# GPIO.net
KiCad netlist of a schematic drawn in Altium Designer
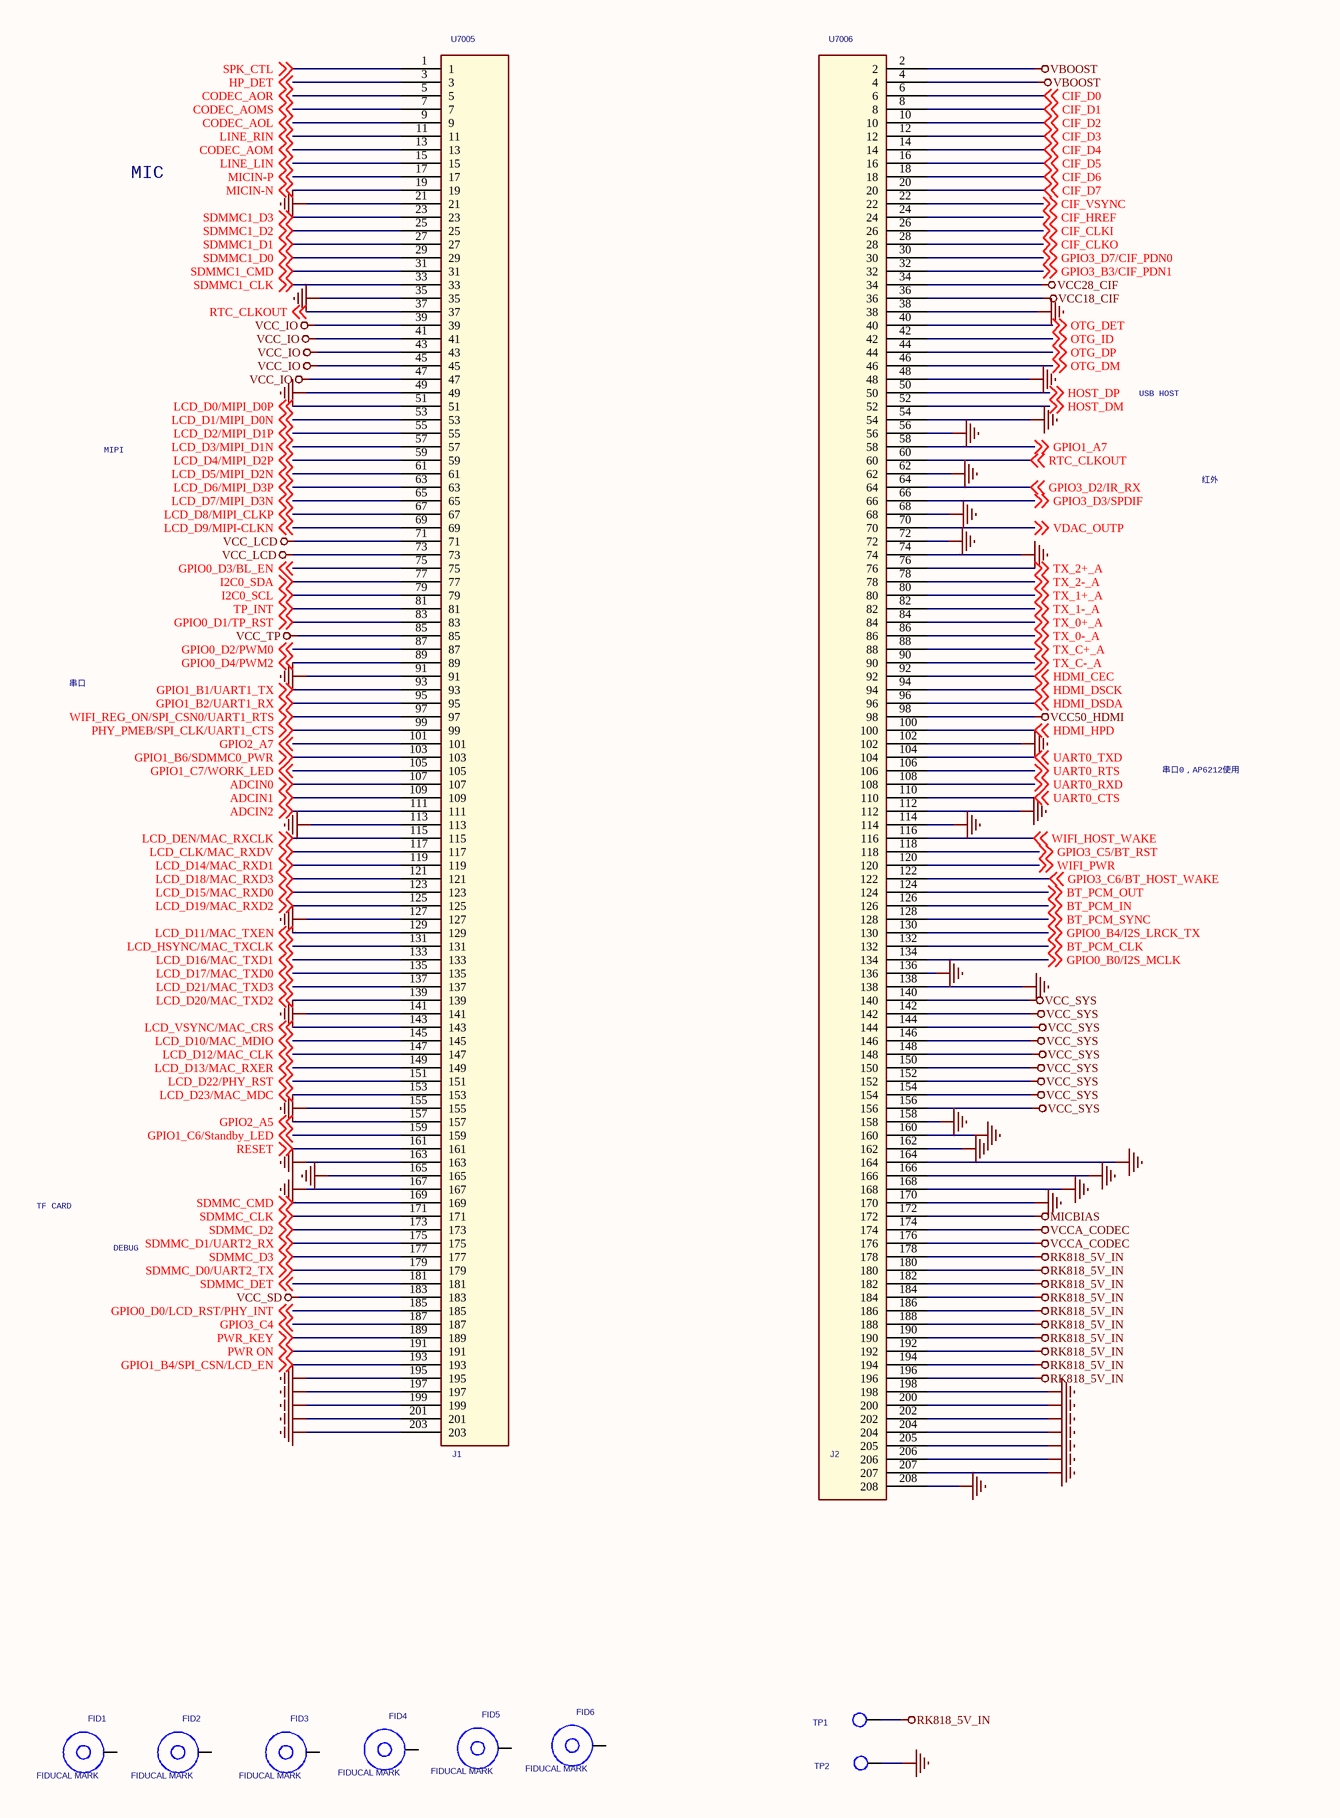
[diagram p0: GPIO.SchDoc, left]
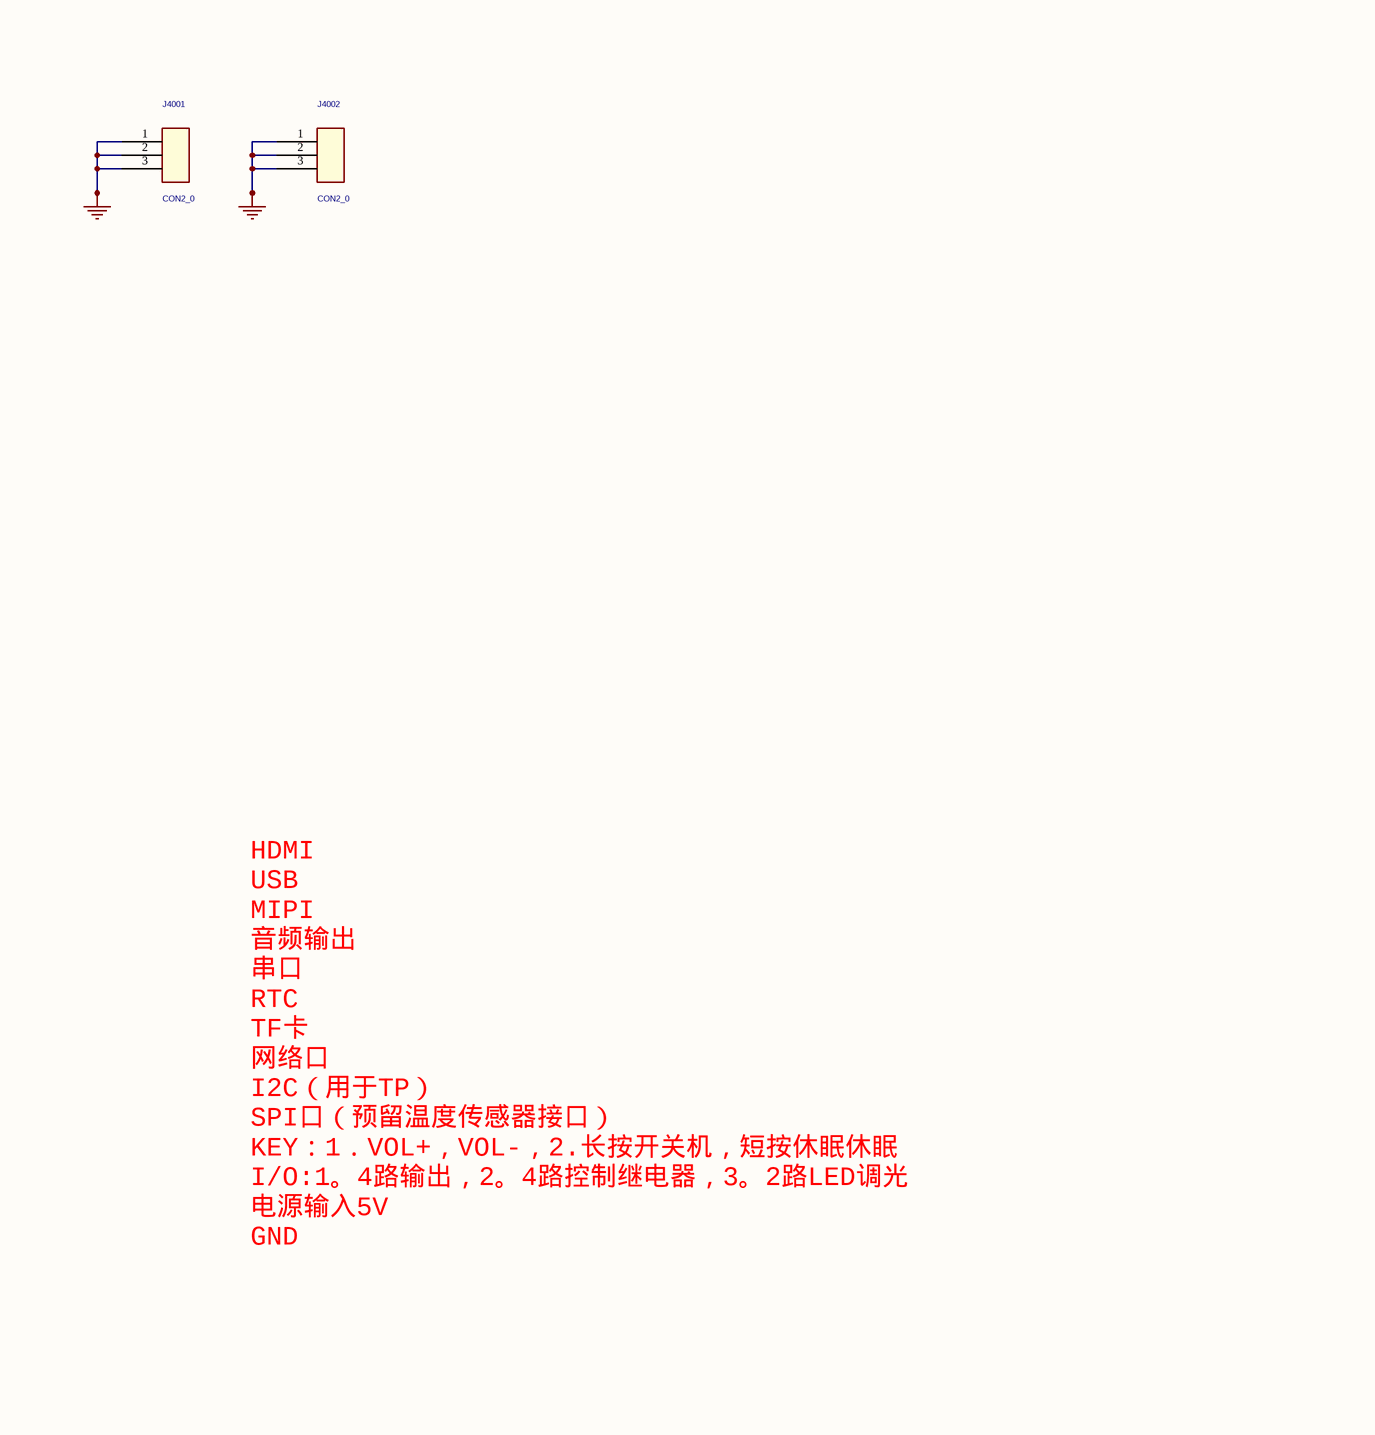
[diagram p1: GPIO.SchDoc, right]

(export (version "E")
  (design (tool "Eeschema 10.0.6"))
  (components
    (comp (ref "FID1")
      (value "FIDUCAL MARK")
      (footprint "FIDICALMARK")
      (libsource (lib "*") (part "T POINT R_2"))
    )
    (comp (ref "FID2")
      (value "FIDUCAL MARK")
      (footprint "FIDICALMARK")
      (libsource (lib "*") (part "T POINT R_2"))
    )
    (comp (ref "FID3")
      (value "FIDUCAL MARK")
      (footprint "FIDICALMARK")
      (libsource (lib "*") (part "T POINT R_2"))
    )
    (comp (ref "FID4")
      (value "FIDUCAL MARK")
      (footprint "FIDICALMARK")
      (libsource (lib "*") (part "T POINT R_2"))
    )
    (comp (ref "FID5")
      (value "FIDUCAL MARK")
      (footprint "FIDICALMARK")
      (libsource (lib "*") (part "T POINT R_2"))
    )
    (comp (ref "FID6")
      (value "FIDUCAL MARK")
      (footprint "FIDICALMARK")
      (libsource (lib "*") (part "T POINT R_2"))
    )
    (comp (ref "J4001") (value "CON2_0") (footprint "PAD_0D8X6D5_1") (libsource (lib "*") (part "CON2_1")))
    (comp (ref "J4002") (value "CON2_0") (footprint "PAD_0D8X6D5_1") (libsource (lib "*") (part "CON2_1")))
    (comp (ref "TP1") (value "T_POINT_R") (footprint "TP_PAD") (libsource (lib "*") (part "T_POINT_R")))
    (comp (ref "TP2") (value "T_POINT_R") (footprint "TP_PAD") (libsource (lib "*") (part "T_POINT_R")))
    (comp (ref "U7005") (value "J1") (footprint "2013311-1") (libsource (lib "*") (part "J1_0")))
    (comp (ref "U7006") (value "J2") (footprint "2013311-2") (libsource (lib "*") (part "J2_1")))
  )
  (nets
    (net (code "1") (name "ADCIN0") (class "Default")
      (node (ref "U7005") (pin "107") (pinfunction "107_107") (pintype "passive"))
    )
    (net (code "2") (name "ADCIN1") (class "Default")
      (node (ref "U7005") (pin "109") (pinfunction "109_109") (pintype "passive"))
    )
    (net (code "3") (name "ADCIN2") (class "Default")
      (node (ref "U7005") (pin "111") (pinfunction "111_111") (pintype "passive"))
    )
    (net (code "4") (name "BT_PCM_CLK") (class "Default")
      (node (ref "U7006") (pin "132") (pinfunction "132_132") (pintype "passive"))
    )
    (net (code "5") (name "BT_PCM_IN") (class "Default")
      (node (ref "U7006") (pin "126") (pinfunction "126_126") (pintype "passive"))
    )
    (net (code "6") (name "BT_PCM_OUT") (class "Default")
      (node (ref "U7006") (pin "124") (pinfunction "124_124") (pintype "passive"))
    )
    (net (code "7") (name "BT_PCM_SYNC") (class "Default")
      (node (ref "U7006") (pin "128") (pinfunction "128_128") (pintype "passive"))
    )
    (net (code "8") (name "CIF_CLKI") (class "Default")
      (node (ref "U7006") (pin "26") (pinfunction "26_26") (pintype "passive"))
    )
    (net (code "9") (name "CIF_CLKO") (class "Default")
      (node (ref "U7006") (pin "28") (pinfunction "28_28") (pintype "passive"))
    )
    (net (code "10") (name "CIF_D0") (class "Default")
      (node (ref "U7006") (pin "6") (pinfunction "6_6") (pintype "passive"))
    )
    (net (code "11") (name "CIF_D1") (class "Default")
      (node (ref "U7006") (pin "8") (pinfunction "8_8") (pintype "passive"))
    )
    (net (code "12") (name "CIF_D2") (class "Default")
      (node (ref "U7006") (pin "10") (pinfunction "10_10") (pintype "passive"))
    )
    (net (code "13") (name "CIF_D3") (class "Default")
      (node (ref "U7006") (pin "12") (pinfunction "12_12") (pintype "passive"))
    )
    (net (code "14") (name "CIF_D4") (class "Default")
      (node (ref "U7006") (pin "14") (pinfunction "14_14") (pintype "passive"))
    )
    (net (code "15") (name "CIF_D5") (class "Default")
      (node (ref "U7006") (pin "16") (pinfunction "16_16") (pintype "passive"))
    )
    (net (code "16") (name "CIF_D6") (class "Default")
      (node (ref "U7006") (pin "18") (pinfunction "18_18") (pintype "passive"))
    )
    (net (code "17") (name "CIF_D7") (class "Default")
      (node (ref "U7006") (pin "20") (pinfunction "20_20") (pintype "passive"))
    )
    (net (code "18") (name "CIF_HREF") (class "Default")
      (node (ref "U7006") (pin "24") (pinfunction "24_24") (pintype "passive"))
    )
    (net (code "19") (name "CIF_VSYNC") (class "Default")
      (node (ref "U7006") (pin "22") (pinfunction "22_22") (pintype "passive"))
    )
    (net (code "20") (name "CODEC_AOL") (class "Default")
      (node (ref "U7005") (pin "9") (pinfunction "9_9") (pintype "passive"))
    )
    (net (code "21") (name "CODEC_AOM") (class "Default")
      (node (ref "U7005") (pin "13") (pinfunction "13_13") (pintype "passive"))
    )
    (net (code "22") (name "CODEC_AOMS") (class "Default")
      (node (ref "U7005") (pin "7") (pinfunction "7_7") (pintype "passive"))
    )
    (net (code "23") (name "CODEC_AOR") (class "Default")
      (node (ref "U7005") (pin "5") (pinfunction "5_5") (pintype "passive"))
    )
    (net (code "24") (name "GND") (class "Default")
      (node (ref "J4001") (pin "1") (pinfunction "1_1") (pintype "passive"))
      (node (ref "J4001") (pin "2") (pinfunction "2_2") (pintype "passive"))
      (node (ref "J4001") (pin "3") (pinfunction "3_3") (pintype "passive"))
      (node (ref "J4002") (pin "1") (pinfunction "1_1") (pintype "passive"))
      (node (ref "J4002") (pin "2") (pinfunction "2_2") (pintype "passive"))
      (node (ref "J4002") (pin "3") (pinfunction "3_3") (pintype "passive"))
      (node (ref "TP2") (pin "1") (pinfunction "TP_1") (pintype "passive"))
      (node (ref "U7005") (pin "113") (pinfunction "113_113") (pintype "passive"))
      (node (ref "U7005") (pin "127") (pinfunction "127_127") (pintype "passive"))
      (node (ref "U7005") (pin "141") (pinfunction "141_141") (pintype "passive"))
      (node (ref "U7005") (pin "155") (pinfunction "155_155") (pintype "passive"))
      (node (ref "U7005") (pin "163") (pinfunction "163_163") (pintype "passive"))
      (node (ref "U7005") (pin "165") (pinfunction "165_165") (pintype "passive"))
      (node (ref "U7005") (pin "167") (pinfunction "167_167") (pintype "passive"))
      (node (ref "U7005") (pin "195") (pinfunction "195_195") (pintype "passive"))
      (node (ref "U7005") (pin "197") (pinfunction "197_197") (pintype "passive"))
      (node (ref "U7005") (pin "199") (pinfunction "199_199") (pintype "passive"))
      (node (ref "U7005") (pin "201") (pinfunction "201_201") (pintype "passive"))
      (node (ref "U7005") (pin "203") (pinfunction "203_203") (pintype "passive"))
      (node (ref "U7005") (pin "21") (pinfunction "21_21") (pintype "passive"))
      (node (ref "U7005") (pin "35") (pinfunction "35_35") (pintype "passive"))
      (node (ref "U7005") (pin "49") (pinfunction "49_49") (pintype "passive"))
      (node (ref "U7005") (pin "91") (pinfunction "91_91") (pintype "passive"))
      (node (ref "U7006") (pin "102") (pinfunction "102_102") (pintype "passive"))
      (node (ref "U7006") (pin "112") (pinfunction "112_112") (pintype "passive"))
      (node (ref "U7006") (pin "114") (pinfunction "114_114") (pintype "passive"))
      (node (ref "U7006") (pin "136") (pinfunction "136_136") (pintype "passive"))
      (node (ref "U7006") (pin "138") (pinfunction "138_138") (pintype "passive"))
      (node (ref "U7006") (pin "158") (pinfunction "158_158") (pintype "passive"))
      (node (ref "U7006") (pin "160") (pinfunction "160_160") (pintype "passive"))
      (node (ref "U7006") (pin "162") (pinfunction "162_162") (pintype "passive"))
      (node (ref "U7006") (pin "164") (pinfunction "164_164") (pintype "passive"))
      (node (ref "U7006") (pin "166") (pinfunction "166_166") (pintype "passive"))
      (node (ref "U7006") (pin "168") (pinfunction "168_168") (pintype "passive"))
      (node (ref "U7006") (pin "170") (pinfunction "170_170") (pintype "passive"))
      (node (ref "U7006") (pin "198") (pinfunction "198_198") (pintype "passive"))
      (node (ref "U7006") (pin "200") (pinfunction "200_200") (pintype "passive"))
      (node (ref "U7006") (pin "202") (pinfunction "202_202") (pintype "passive"))
      (node (ref "U7006") (pin "204") (pinfunction "204_204") (pintype "passive"))
      (node (ref "U7006") (pin "205") (pinfunction "205_205") (pintype "passive"))
      (node (ref "U7006") (pin "206") (pinfunction "206_206") (pintype "passive"))
      (node (ref "U7006") (pin "207") (pinfunction "207_207") (pintype "passive"))
      (node (ref "U7006") (pin "208") (pinfunction "208_208") (pintype "passive"))
      (node (ref "U7006") (pin "38") (pinfunction "38_38") (pintype "passive"))
      (node (ref "U7006") (pin "48") (pinfunction "48_48") (pintype "passive"))
      (node (ref "U7006") (pin "54") (pinfunction "54_54") (pintype "passive"))
      (node (ref "U7006") (pin "56") (pinfunction "56_56") (pintype "passive"))
      (node (ref "U7006") (pin "62") (pinfunction "62_62") (pintype "passive"))
      (node (ref "U7006") (pin "68") (pinfunction "68_68") (pintype "passive"))
      (node (ref "U7006") (pin "72") (pinfunction "72_72") (pintype "passive"))
      (node (ref "U7006") (pin "74") (pinfunction "74_74") (pintype "passive"))
    )
    (net (code "25") (name "GPIO0_B0{slash}I2S_MCLK") (class "Default")
      (node (ref "U7006") (pin "134") (pinfunction "134_134") (pintype "passive"))
    )
    (net (code "26") (name "GPIO0_B4{slash}I2S_LRCK_TX") (class "Default")
      (node (ref "U7006") (pin "130") (pinfunction "130_130") (pintype "passive"))
    )
    (net (code "27") (name "GPIO0_D0{slash}LCD_RST{slash}PHY_INT") (class "Default")
      (node (ref "U7005") (pin "185") (pinfunction "185_185") (pintype "passive"))
    )
    (net (code "28") (name "GPIO0_D1{slash}TP_RST") (class "Default")
      (node (ref "U7005") (pin "83") (pinfunction "83_83") (pintype "passive"))
    )
    (net (code "29") (name "GPIO0_D2{slash}PWM0") (class "Default")
      (node (ref "U7005") (pin "87") (pinfunction "87_87") (pintype "passive"))
    )
    (net (code "30") (name "GPIO0_D3{slash}BL_EN") (class "Default")
      (node (ref "U7005") (pin "75") (pinfunction "75_75") (pintype "passive"))
    )
    (net (code "31") (name "GPIO0_D4{slash}PWM2") (class "Default")
      (node (ref "U7005") (pin "89") (pinfunction "89_89") (pintype "passive"))
    )
    (net (code "32") (name "GPIO1_A7") (class "Default")
      (node (ref "U7006") (pin "58") (pinfunction "58_58") (pintype "passive"))
    )
    (net (code "33") (name "GPIO1_B1{slash}UART1_TX") (class "Default")
      (node (ref "U7005") (pin "93") (pinfunction "93_93") (pintype "passive"))
    )
    (net (code "34") (name "GPIO1_B2{slash}UART1_RX") (class "Default")
      (node (ref "U7005") (pin "95") (pinfunction "95_95") (pintype "passive"))
    )
    (net (code "35") (name "GPIO1_B4{slash}SPI_CSN{slash}LCD_EN") (class "Default")
      (node (ref "U7005") (pin "193") (pinfunction "193_193") (pintype "passive"))
    )
    (net (code "36") (name "GPIO1_B6{slash}SDMMC0_PWR") (class "Default")
      (node (ref "U7005") (pin "103") (pinfunction "103_103") (pintype "passive"))
    )
    (net (code "37") (name "GPIO1_C6{slash}Standby_LED") (class "Default")
      (node (ref "U7005") (pin "159") (pinfunction "159_159") (pintype "passive"))
    )
    (net (code "38") (name "GPIO1_C7{slash}WORK_LED") (class "Default")
      (node (ref "U7005") (pin "105") (pinfunction "105_105") (pintype "passive"))
    )
    (net (code "39") (name "GPIO2_A5") (class "Default")
      (node (ref "U7005") (pin "157") (pinfunction "157_157") (pintype "passive"))
    )
    (net (code "40") (name "GPIO2_A7") (class "Default")
      (node (ref "U7005") (pin "101") (pinfunction "101_101") (pintype "passive"))
    )
    (net (code "41") (name "GPIO3_B3{slash}CIF_PDN1") (class "Default")
      (node (ref "U7006") (pin "32") (pinfunction "32_32") (pintype "passive"))
    )
    (net (code "42") (name "GPIO3_C4") (class "Default")
      (node (ref "U7005") (pin "187") (pinfunction "187_187") (pintype "passive"))
    )
    (net (code "43") (name "GPIO3_C5{slash}BT_RST") (class "Default")
      (node (ref "U7006") (pin "118") (pinfunction "118_118") (pintype "passive"))
    )
    (net (code "44") (name "GPIO3_C6{slash}BT_HOST_WAKE") (class "Default")
      (node (ref "U7006") (pin "122") (pinfunction "122_122") (pintype "passive"))
    )
    (net (code "45") (name "GPIO3_D2{slash}IR_RX") (class "Default")
      (node (ref "U7006") (pin "64") (pinfunction "64_64") (pintype "passive"))
    )
    (net (code "46") (name "GPIO3_D3{slash}SPDIF") (class "Default")
      (node (ref "U7006") (pin "66") (pinfunction "66_66") (pintype "passive"))
    )
    (net (code "47") (name "GPIO3_D7{slash}CIF_PDN0") (class "Default")
      (node (ref "U7006") (pin "30") (pinfunction "30_30") (pintype "passive"))
    )
    (net (code "48") (name "HDMI_CEC") (class "Default")
      (node (ref "U7006") (pin "92") (pinfunction "92_92") (pintype "passive"))
    )
    (net (code "49") (name "HDMI_DSCK") (class "Default")
      (node (ref "U7006") (pin "94") (pinfunction "94_94") (pintype "passive"))
    )
    (net (code "50") (name "HDMI_DSDA") (class "Default")
      (node (ref "U7006") (pin "96") (pinfunction "96_96") (pintype "passive"))
    )
    (net (code "51") (name "HDMI_HPD") (class "Default")
      (node (ref "U7006") (pin "100") (pinfunction "100_100") (pintype "passive"))
    )
    (net (code "52") (name "HOST_DM") (class "Default")
      (node (ref "U7006") (pin "52") (pinfunction "52_52") (pintype "passive"))
    )
    (net (code "53") (name "HOST_DP") (class "Default")
      (node (ref "U7006") (pin "50") (pinfunction "50_50") (pintype "passive"))
    )
    (net (code "54") (name "HP_DET") (class "Default")
      (node (ref "U7005") (pin "3") (pinfunction "3_3") (pintype "passive"))
    )
    (net (code "55") (name "I2C0_SCL") (class "Default")
      (node (ref "U7005") (pin "79") (pinfunction "79_79") (pintype "passive"))
    )
    (net (code "56") (name "I2C0_SDA") (class "Default")
      (node (ref "U7005") (pin "77") (pinfunction "77_77") (pintype "passive"))
    )
    (net (code "57") (name "LCD_CLK{slash}MAC_RXDV") (class "Default")
      (node (ref "U7005") (pin "117") (pinfunction "117_117") (pintype "passive"))
    )
    (net (code "58") (name "LCD_D0{slash}MIPI_D0P") (class "Default")
      (node (ref "U7005") (pin "51") (pinfunction "51_51") (pintype "passive"))
    )
    (net (code "59") (name "LCD_D1{slash}MIPI_D0N") (class "Default")
      (node (ref "U7005") (pin "53") (pinfunction "53_53") (pintype "passive"))
    )
    (net (code "60") (name "LCD_D2{slash}MIPI_D1P") (class "Default")
      (node (ref "U7005") (pin "55") (pinfunction "55_55") (pintype "passive"))
    )
    (net (code "61") (name "LCD_D3{slash}MIPI_D1N") (class "Default")
      (node (ref "U7005") (pin "57") (pinfunction "57_57") (pintype "passive"))
    )
    (net (code "62") (name "LCD_D4{slash}MIPI_D2P") (class "Default")
      (node (ref "U7005") (pin "59") (pinfunction "59_59") (pintype "passive"))
    )
    (net (code "63") (name "LCD_D5{slash}MIPI_D2N") (class "Default")
      (node (ref "U7005") (pin "61") (pinfunction "61_61") (pintype "passive"))
    )
    (net (code "64") (name "LCD_D6{slash}MIPI_D3P") (class "Default")
      (node (ref "U7005") (pin "63") (pinfunction "63_63") (pintype "passive"))
    )
    (net (code "65") (name "LCD_D7{slash}MIPI_D3N") (class "Default")
      (node (ref "U7005") (pin "65") (pinfunction "65_65") (pintype "passive"))
    )
    (net (code "66") (name "LCD_D8{slash}MIPI_CLKP") (class "Default")
      (node (ref "U7005") (pin "67") (pinfunction "67_67") (pintype "passive"))
    )
    (net (code "67") (name "LCD_D9{slash}MIPI-CLKN") (class "Default")
      (node (ref "U7005") (pin "69") (pinfunction "69_69") (pintype "passive"))
    )
    (net (code "68") (name "LCD_D10{slash}MAC_MDIO") (class "Default")
      (node (ref "U7005") (pin "145") (pinfunction "145_145") (pintype "passive"))
    )
    (net (code "69") (name "LCD_D11{slash}MAC_TXEN") (class "Default")
      (node (ref "U7005") (pin "129") (pinfunction "129_129") (pintype "passive"))
    )
    (net (code "70") (name "LCD_D12{slash}MAC_CLK") (class "Default")
      (node (ref "U7005") (pin "147") (pinfunction "147_147") (pintype "passive"))
    )
    (net (code "71") (name "LCD_D13{slash}MAC_RXER") (class "Default")
      (node (ref "U7005") (pin "149") (pinfunction "149_149") (pintype "passive"))
    )
    (net (code "72") (name "LCD_D14{slash}MAC_RXD1") (class "Default")
      (node (ref "U7005") (pin "119") (pinfunction "119_119") (pintype "passive"))
    )
    (net (code "73") (name "LCD_D15{slash}MAC_RXD0") (class "Default")
      (node (ref "U7005") (pin "123") (pinfunction "123_123") (pintype "passive"))
    )
    (net (code "74") (name "LCD_D16{slash}MAC_TXD1") (class "Default")
      (node (ref "U7005") (pin "133") (pinfunction "133_133") (pintype "passive"))
    )
    (net (code "75") (name "LCD_D17{slash}MAC_TXD0") (class "Default")
      (node (ref "U7005") (pin "135") (pinfunction "135_135") (pintype "passive"))
    )
    (net (code "76") (name "LCD_D18{slash}MAC_RXD3") (class "Default")
      (node (ref "U7005") (pin "121") (pinfunction "121_121") (pintype "passive"))
    )
    (net (code "77") (name "LCD_D19{slash}MAC_RXD2") (class "Default")
      (node (ref "U7005") (pin "125") (pinfunction "125_125") (pintype "passive"))
    )
    (net (code "78") (name "LCD_D20{slash}MAC_TXD2") (class "Default")
      (node (ref "U7005") (pin "139") (pinfunction "139_139") (pintype "passive"))
    )
    (net (code "79") (name "LCD_D21{slash}MAC_TXD3") (class "Default")
      (node (ref "U7005") (pin "137") (pinfunction "137_137") (pintype "passive"))
    )
    (net (code "80") (name "LCD_D22{slash}PHY_RST") (class "Default")
      (node (ref "U7005") (pin "151") (pinfunction "151_151") (pintype "passive"))
    )
    (net (code "81") (name "LCD_D23{slash}MAC_MDC") (class "Default")
      (node (ref "U7005") (pin "153") (pinfunction "153_153") (pintype "passive"))
    )
    (net (code "82") (name "LCD_DEN{slash}MAC_RXCLK") (class "Default")
      (node (ref "U7005") (pin "115") (pinfunction "115_115") (pintype "passive"))
    )
    (net (code "83") (name "LCD_HSYNC{slash}MAC_TXCLK") (class "Default")
      (node (ref "U7005") (pin "131") (pinfunction "131_131") (pintype "passive"))
    )
    (net (code "84") (name "LCD_VSYNC{slash}MAC_CRS") (class "Default")
      (node (ref "U7005") (pin "143") (pinfunction "143_143") (pintype "passive"))
    )
    (net (code "85") (name "LINE_LIN") (class "Default")
      (node (ref "U7005") (pin "15") (pinfunction "15_15") (pintype "passive"))
    )
    (net (code "86") (name "LINE_RIN") (class "Default")
      (node (ref "U7005") (pin "11") (pinfunction "11_11") (pintype "passive"))
    )
    (net (code "87") (name "MICBIAS") (class "Default")
      (node (ref "U7006") (pin "172") (pinfunction "172_172") (pintype "passive"))
    )
    (net (code "88") (name "MICIN-N") (class "Default")
      (node (ref "U7005") (pin "19") (pinfunction "19_19") (pintype "passive"))
    )
    (net (code "89") (name "MICIN-P") (class "Default")
      (node (ref "U7005") (pin "17") (pinfunction "17_17") (pintype "passive"))
    )
    (net (code "90") (name "OTG_DET") (class "Default")
      (node (ref "U7006") (pin "40") (pinfunction "40_40") (pintype "passive"))
    )
    (net (code "91") (name "OTG_DM") (class "Default")
      (node (ref "U7006") (pin "46") (pinfunction "46_46") (pintype "passive"))
    )
    (net (code "92") (name "OTG_DP") (class "Default")
      (node (ref "U7006") (pin "44") (pinfunction "44_44") (pintype "passive"))
    )
    (net (code "93") (name "OTG_ID") (class "Default")
      (node (ref "U7006") (pin "42") (pinfunction "42_42") (pintype "passive"))
    )
    (net (code "94") (name "PHY_PMEB{slash}SPI_CLK{slash}UART1_CTS") (class "Default")
      (node (ref "U7005") (pin "99") (pinfunction "99_99") (pintype "passive"))
    )
    (net (code "95") (name "PWR ON") (class "Default")
      (node (ref "U7005") (pin "191") (pinfunction "191_191") (pintype "passive"))
    )
    (net (code "96") (name "PWR_KEY") (class "Default")
      (node (ref "U7005") (pin "189") (pinfunction "189_189") (pintype "passive"))
    )
    (net (code "97") (name "RESET") (class "Default")
      (node (ref "U7005") (pin "161") (pinfunction "161_161") (pintype "passive"))
    )
    (net (code "98") (name "RK818_5V_IN") (class "Default")
      (node (ref "TP1") (pin "1") (pinfunction "TP_1") (pintype "passive"))
      (node (ref "U7006") (pin "178") (pinfunction "178_178") (pintype "passive"))
      (node (ref "U7006") (pin "180") (pinfunction "180_180") (pintype "passive"))
      (node (ref "U7006") (pin "182") (pinfunction "182_182") (pintype "passive"))
      (node (ref "U7006") (pin "184") (pinfunction "184_184") (pintype "passive"))
      (node (ref "U7006") (pin "186") (pinfunction "186_186") (pintype "passive"))
      (node (ref "U7006") (pin "188") (pinfunction "188_188") (pintype "passive"))
      (node (ref "U7006") (pin "190") (pinfunction "190_190") (pintype "passive"))
      (node (ref "U7006") (pin "192") (pinfunction "192_192") (pintype "passive"))
      (node (ref "U7006") (pin "194") (pinfunction "194_194") (pintype "passive"))
      (node (ref "U7006") (pin "196") (pinfunction "196_196") (pintype "passive"))
    )
    (net (code "99") (name "RTC_CLKOUT") (class "Default")
      (node (ref "U7005") (pin "37") (pinfunction "37_37") (pintype "passive"))
      (node (ref "U7006") (pin "60") (pinfunction "60_60") (pintype "passive"))
    )
    (net (code "100") (name "SDMMC1_CLK") (class "Default")
      (node (ref "U7005") (pin "33") (pinfunction "33_33") (pintype "passive"))
    )
    (net (code "101") (name "SDMMC1_CMD") (class "Default")
      (node (ref "U7005") (pin "31") (pinfunction "31_31") (pintype "passive"))
    )
    (net (code "102") (name "SDMMC1_D0") (class "Default")
      (node (ref "U7005") (pin "29") (pinfunction "29_29") (pintype "passive"))
    )
    (net (code "103") (name "SDMMC1_D1") (class "Default")
      (node (ref "U7005") (pin "27") (pinfunction "27_27") (pintype "passive"))
    )
    (net (code "104") (name "SDMMC1_D2") (class "Default")
      (node (ref "U7005") (pin "25") (pinfunction "25_25") (pintype "passive"))
    )
    (net (code "105") (name "SDMMC1_D3") (class "Default")
      (node (ref "U7005") (pin "23") (pinfunction "23_23") (pintype "passive"))
    )
    (net (code "106") (name "SDMMC_CLK") (class "Default")
      (node (ref "U7005") (pin "171") (pinfunction "171_171") (pintype "passive"))
    )
    (net (code "107") (name "SDMMC_CMD") (class "Default")
      (node (ref "U7005") (pin "169") (pinfunction "169_169") (pintype "passive"))
    )
    (net (code "108") (name "SDMMC_D0{slash}UART2_TX") (class "Default")
      (node (ref "U7005") (pin "179") (pinfunction "179_179") (pintype "passive"))
    )
    (net (code "109") (name "SDMMC_D1{slash}UART2_RX") (class "Default")
      (node (ref "U7005") (pin "175") (pinfunction "175_175") (pintype "passive"))
    )
    (net (code "110") (name "SDMMC_D2") (class "Default")
      (node (ref "U7005") (pin "173") (pinfunction "173_173") (pintype "passive"))
    )
    (net (code "111") (name "SDMMC_D3") (class "Default")
      (node (ref "U7005") (pin "177") (pinfunction "177_177") (pintype "passive"))
    )
    (net (code "112") (name "SDMMC_DET") (class "Default")
      (node (ref "U7005") (pin "181") (pinfunction "181_181") (pintype "passive"))
    )
    (net (code "113") (name "SPK_CTL") (class "Default")
      (node (ref "U7005") (pin "1") (pinfunction "1_1") (pintype "passive"))
    )
    (net (code "114") (name "TP_INT") (class "Default")
      (node (ref "U7005") (pin "81") (pinfunction "81_81") (pintype "passive"))
    )
    (net (code "115") (name "TX_0+_A") (class "Default")
      (node (ref "U7006") (pin "84") (pinfunction "84_84") (pintype "passive"))
    )
    (net (code "116") (name "TX_0-_A") (class "Default")
      (node (ref "U7006") (pin "86") (pinfunction "86_86") (pintype "passive"))
    )
    (net (code "117") (name "TX_1+_A") (class "Default")
      (node (ref "U7006") (pin "80") (pinfunction "80_80") (pintype "passive"))
    )
    (net (code "118") (name "TX_1-_A") (class "Default")
      (node (ref "U7006") (pin "82") (pinfunction "82_82") (pintype "passive"))
    )
    (net (code "119") (name "TX_2+_A") (class "Default")
      (node (ref "U7006") (pin "76") (pinfunction "76_76") (pintype "passive"))
    )
    (net (code "120") (name "TX_2-_A") (class "Default")
      (node (ref "U7006") (pin "78") (pinfunction "78_78") (pintype "passive"))
    )
    (net (code "121") (name "TX_C+_A") (class "Default")
      (node (ref "U7006") (pin "88") (pinfunction "88_88") (pintype "passive"))
    )
    (net (code "122") (name "TX_C-_A") (class "Default")
      (node (ref "U7006") (pin "90") (pinfunction "90_90") (pintype "passive"))
    )
    (net (code "123") (name "UART0_CTS") (class "Default")
      (node (ref "U7006") (pin "110") (pinfunction "110_110") (pintype "passive"))
    )
    (net (code "124") (name "UART0_RTS") (class "Default")
      (node (ref "U7006") (pin "106") (pinfunction "106_106") (pintype "passive"))
    )
    (net (code "125") (name "UART0_RXD") (class "Default")
      (node (ref "U7006") (pin "108") (pinfunction "108_108") (pintype "passive"))
    )
    (net (code "126") (name "UART0_TXD") (class "Default")
      (node (ref "U7006") (pin "104") (pinfunction "104_104") (pintype "passive"))
    )
    (net (code "127") (name "VBOOST") (class "Default")
      (node (ref "U7006") (pin "2") (pinfunction "2_2") (pintype "passive"))
      (node (ref "U7006") (pin "4") (pinfunction "4_4") (pintype "passive"))
    )
    (net (code "128") (name "VCC18_CIF") (class "Default")
      (node (ref "U7006") (pin "36") (pinfunction "36_36") (pintype "passive"))
    )
    (net (code "129") (name "VCC28_CIF") (class "Default")
      (node (ref "U7006") (pin "34") (pinfunction "34_34") (pintype "passive"))
    )
    (net (code "130") (name "VCC50_HDMI") (class "Default")
      (node (ref "U7006") (pin "98") (pinfunction "98_98") (pintype "passive"))
    )
    (net (code "131") (name "VCCA_CODEC") (class "Default")
      (node (ref "U7006") (pin "174") (pinfunction "174_174") (pintype "passive"))
      (node (ref "U7006") (pin "176") (pinfunction "176_176") (pintype "passive"))
    )
    (net (code "132") (name "VCC_IO") (class "Default")
      (node (ref "U7005") (pin "39") (pinfunction "39_39") (pintype "passive"))
      (node (ref "U7005") (pin "41") (pinfunction "41_41") (pintype "passive"))
      (node (ref "U7005") (pin "43") (pinfunction "43_43") (pintype "passive"))
      (node (ref "U7005") (pin "45") (pinfunction "45_45") (pintype "passive"))
      (node (ref "U7005") (pin "47") (pinfunction "47_47") (pintype "passive"))
    )
    (net (code "133") (name "VCC_LCD") (class "Default")
      (node (ref "U7005") (pin "71") (pinfunction "71_71") (pintype "passive"))
      (node (ref "U7005") (pin "73") (pinfunction "73_73") (pintype "passive"))
    )
    (net (code "134") (name "VCC_SD") (class "Default")
      (node (ref "U7005") (pin "183") (pinfunction "183_183") (pintype "passive"))
    )
    (net (code "135") (name "VCC_SYS") (class "Default")
      (node (ref "U7006") (pin "140") (pinfunction "140_140") (pintype "passive"))
      (node (ref "U7006") (pin "142") (pinfunction "142_142") (pintype "passive"))
      (node (ref "U7006") (pin "144") (pinfunction "144_144") (pintype "passive"))
      (node (ref "U7006") (pin "146") (pinfunction "146_146") (pintype "passive"))
      (node (ref "U7006") (pin "148") (pinfunction "148_148") (pintype "passive"))
      (node (ref "U7006") (pin "150") (pinfunction "150_150") (pintype "passive"))
      (node (ref "U7006") (pin "152") (pinfunction "152_152") (pintype "passive"))
      (node (ref "U7006") (pin "154") (pinfunction "154_154") (pintype "passive"))
      (node (ref "U7006") (pin "156") (pinfunction "156_156") (pintype "passive"))
    )
    (net (code "136") (name "VCC_TP") (class "Default")
      (node (ref "U7005") (pin "85") (pinfunction "85_85") (pintype "passive"))
    )
    (net (code "137") (name "VDAC_OUTP") (class "Default")
      (node (ref "U7006") (pin "70") (pinfunction "70_70") (pintype "passive"))
    )
    (net (code "138") (name "WIFI_HOST_WAKE") (class "Default")
      (node (ref "U7006") (pin "116") (pinfunction "116_116") (pintype "passive"))
    )
    (net (code "139") (name "WIFI_PWR") (class "Default")
      (node (ref "U7006") (pin "120") (pinfunction "120_120") (pintype "passive"))
    )
    (net (code "140") (name "WIFI_REG_ON{slash}SPI_CSN0{slash}UART1_RTS") (class "Default")
      (node (ref "U7005") (pin "97") (pinfunction "97_97") (pintype "passive"))
    )
    (net (code "141") (name "unconnected-(FID1-TP-Pad1)") (class "Default")
      (node (ref "FID1") (pin "1") (pinfunction "TP_1") (pintype "passive"))
    )
    (net (code "142") (name "unconnected-(FID2-TP-Pad1)") (class "Default")
      (node (ref "FID2") (pin "1") (pinfunction "TP_1") (pintype "passive"))
    )
    (net (code "143") (name "unconnected-(FID3-TP-Pad1)") (class "Default")
      (node (ref "FID3") (pin "1") (pinfunction "TP_1") (pintype "passive"))
    )
    (net (code "144") (name "unconnected-(FID4-TP-Pad1)") (class "Default")
      (node (ref "FID4") (pin "1") (pinfunction "TP_1") (pintype "passive"))
    )
    (net (code "145") (name "unconnected-(FID5-TP-Pad1)") (class "Default")
      (node (ref "FID5") (pin "1") (pinfunction "TP_1") (pintype "passive"))
    )
    (net (code "146") (name "unconnected-(FID6-TP-Pad1)") (class "Default")
      (node (ref "FID6") (pin "1") (pinfunction "TP_1") (pintype "passive"))
    )
  )
)
